# PressureConnector_2.net
KiCad netlist of a schematic drawn in Altium Designer
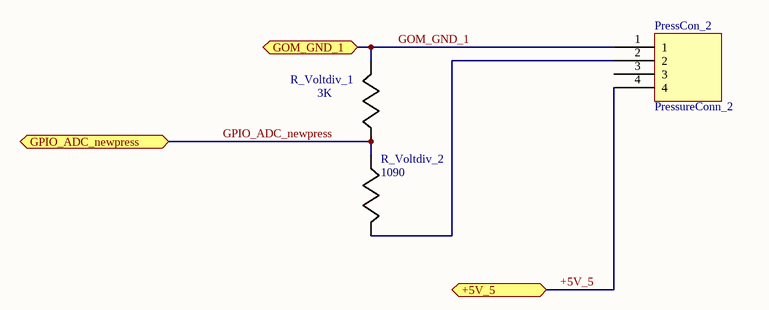
[diagram p0: PressureConnector_2.SchDoc]

(export (version "E")
  (design (tool "Eeschema 10.0.6"))
  (components
    (comp (ref "PressCon_2")
      (value "PressureConn_2")
      (footprint "PressCon_2")
      (libsource (lib "UmbilicalBoardV2") (part "PressureConn_2"))
    )
    (comp (ref "R_Voltdiv_1")
      (value "3K")
      (footprint "0402")
      (description "Imported")
      (fields (field (name "MANUFACTURER_PART_NUMBER") "CRCW040210R0FKED"))
      (libsource (lib "2016-03-26_18-23-46") (part "CRCW040210R0FKED"))
    )
    (comp (ref "R_Voltdiv_2")
      (value "1090")
      (footprint "0402")
      (description "Imported")
      (fields (field (name "MANUFACTURER_PART_NUMBER") "CRCW040210R0FKED"))
      (libsource (lib "2016-03-26_18-23-46") (part "CRCW040210R0FKED"))
    )
  )
  (nets
    (net (code "1") (name "/+5V_5") (class "Default")
      (node (ref "PressCon_2") (pin "4") (pinfunction "4_4") (pintype "passive"))
    )
    (net (code "2") (name "/GOM_GND_1") (class "Default")
      (node (ref "PressCon_2") (pin "1") (pinfunction "1_1") (pintype "passive"))
      (node (ref "R_Voltdiv_1") (pin "1") (pinfunction "1_1") (pintype "passive"))
    )
    (net (code "3") (name "/GPIO_ADC_newpress") (class "Default")
      (node (ref "R_Voltdiv_1") (pin "2") (pinfunction "2_2") (pintype "passive"))
      (node (ref "R_Voltdiv_2") (pin "2") (pinfunction "2_2") (pintype "passive"))
    )
    (net (code "4") (name "Net-(PressCon_2-Pad2)") (class "Default")
      (node (ref "PressCon_2") (pin "2") (pinfunction "2_2") (pintype "passive"))
      (node (ref "R_Voltdiv_2") (pin "1") (pinfunction "1_1") (pintype "passive"))
    )
    (net (code "5") (name "unconnected-(PressCon_2-Pad3)") (class "Default")
      (node (ref "PressCon_2") (pin "3") (pinfunction "3_3") (pintype "passive"))
    )
  )
)
